# BatteryManagementSystemA.net
KiCad netlist of a schematic drawn in Altium Designer
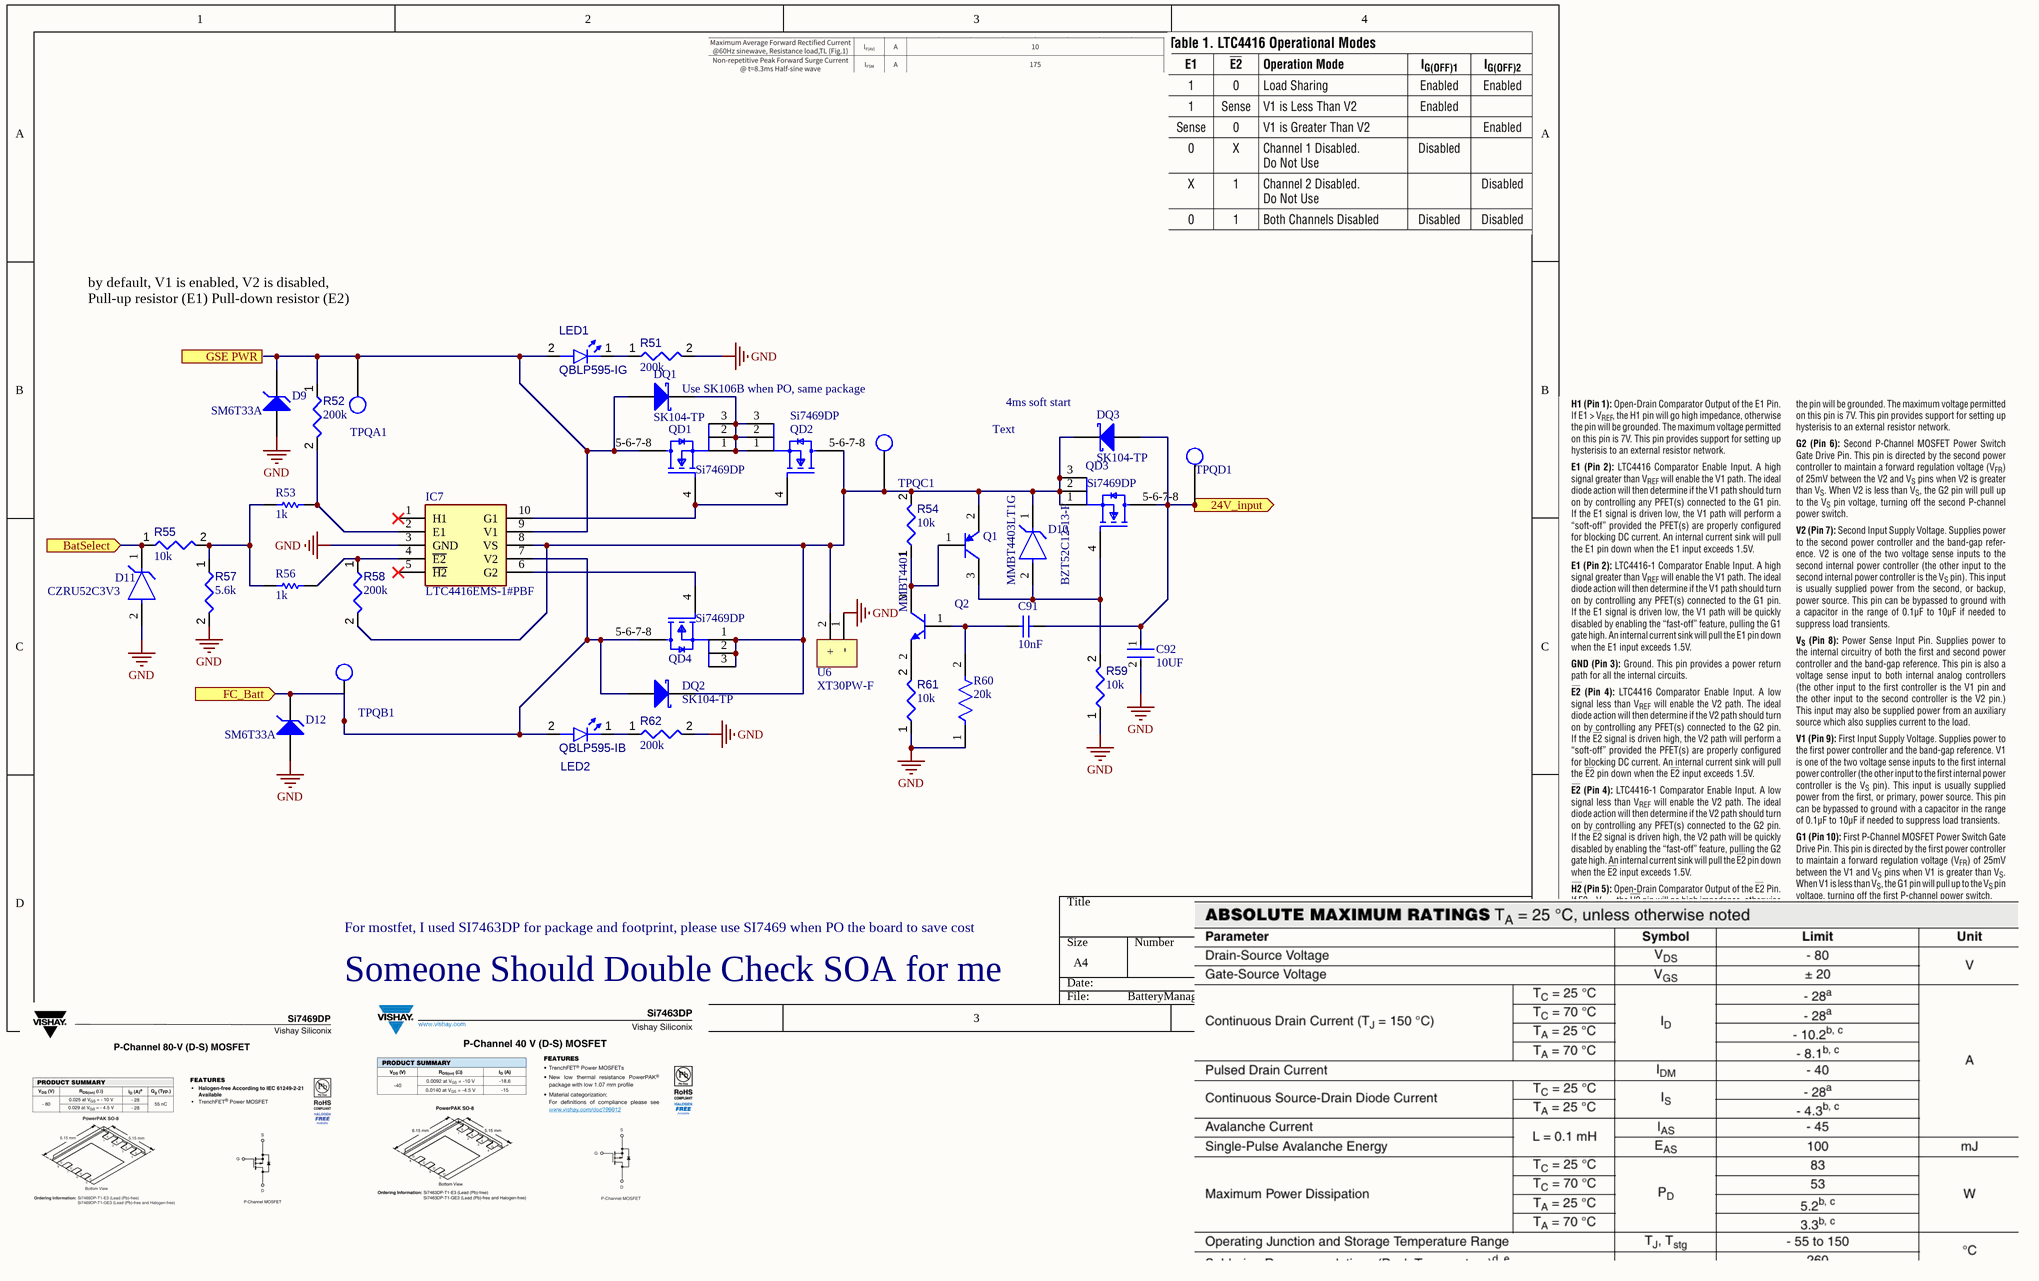
[diagram p0: BatteryManagementSystemA.SchDoc]

(export (version "E")
  (design (tool "Eeschema 10.0.6"))
  (components
    (comp (ref "C91")
      (value "10nF")
      (footprint "CAPC1608X90X35ML10T15")
      (description "Chip Capacitor, 10 nF, +/- 10%, 50 V, -55 to 125 degC, 0603 (1608 Metric), RoHS, Tape and Reel")
      (fields (field (name "VOLTAGE") "50V") (field (name "TOLERANCE") "10%"))
      (libsource (lib "Altium Content Vault") (part "CAP-NP-2"))
    )
    (comp (ref "C92")
      (value "10UF")
      (footprint "FP-GRM31-0_2-MFG")
      (description "CAP CER 10UF 50V X5R 1206")
      (fields
        (field (name "OCTOPART") "https://octopart.com/grm31cr61h106ka12l-murata-18903335")
        (field (name "TOLERANCE") "10%")
      )
      (libsource (lib "Altium Content Vault") (part "11868f565c42a9108669ba33697ecf6"))
    )
    (comp (ref "D9")
      (value "SM6T33A")
      (footprint "STM-SMB_P_V")
      (description "Transil(TM), Uni-Directional, 600 W, -55 to 150 degC, 2-Pin SMB , RoHS, Tape and Reel")
      (fields (field (name "MANUFACTURER") "STMicroelectronics"))
      (libsource (lib "Altium Content Vault") (part "DZEN-KA-2"))
    )
    (comp (ref "D10")
      (value "BZT52C12-13-F")
      (footprint "FP-SOD123-MFG")
      (description "DIODE ZENER 12V 500MW SOD123")
      (fields
        (field (name "OCTOPART") "https://octopart.com/bzt52c12-13-f-diodes+inc.-326533")
        (field (name "MANUFACTURER") "Diodes Inc")
      )
      (libsource (lib "Altium Content Vault") (part "f813f71cba58e380607f5dd3caf9714"))
    )
    (comp (ref "D11")
      (value "CZRU52C3V3")
      (footprint "FP-0603-SOD-523F-MFG")
      (description "DIODE ZENER 3.3V 150MW 0603")
      (fields (field (name "TOLERANCE") "5%"))
      (libsource (lib "Altium Content Vault") (part "f813f71cba58e380607f5dd3caf9714"))
    )
    (comp (ref "D12")
      (value "SM6T33A")
      (footprint "STM-SMB_P_V")
      (description "Transil(TM), Uni-Directional, 600 W, -55 to 150 degC, 2-Pin SMB , RoHS, Tape and Reel")
      (fields (field (name "MANUFACTURER") "STMicroelectronics"))
      (libsource (lib "Altium Content Vault") (part "DZEN-KA-2"))
    )
    (comp (ref "DQ1")
      (value "SK104-TP")
      (footprint "MCC-DO-214AB-2_V")
      (description "Schottky Rectifier, 40 V, 10 A, -55 to 125 degC, 2-Pin SMD, RoHS, Tape and Reel")
      (fields (field (name "MANUFACTURER") "Micro Commercial Components"))
      (libsource (lib "Altium Content Vault") (part "DSKY-AK-2"))
    )
    (comp (ref "DQ2")
      (value "SK104-TP")
      (footprint "MCC-DO-214AB-2_V")
      (description "Schottky Rectifier, 40 V, 10 A, -55 to 125 degC, 2-Pin SMD, RoHS, Tape and Reel")
      (fields (field (name "MANUFACTURER") "Micro Commercial Components"))
      (libsource (lib "Altium Content Vault") (part "DSKY-AK-2"))
    )
    (comp (ref "DQ3")
      (value "SK104-TP")
      (footprint "MCC-DO-214AB-2_V")
      (description "Schottky Rectifier, 40 V, 10 A, -55 to 125 degC, 2-Pin SMD, RoHS, Tape and Reel")
      (fields (field (name "MANUFACTURER") "Micro Commercial Components"))
      (libsource (lib "Altium Content Vault") (part "DSKY-AK-2"))
    )
    (comp (ref "IC7")
      (value "LTC4416EMS-1#PBF")
      (footprint "SamacSys:SOP50P490X110-10N")
      (description "Integrated Circuit")
      (fields (field (name "MOUSER PART NUMBER") "584-LTC4416EMS-1#PBF"))
      (libsource (lib "*") (part "LTC4416EMS-1#PBF"))
    )
    (comp (ref "LED1")
      (value "QBLP595-IG")
      (footprint "QTB-QBLP595_V")
      (description "Chip LED 0402, Green, 0.02 A, 3.1 to 3.7 V, -40 to 80 degC, 2-Pin SMD, RoHS, Tape and Reel")
      (libsource (lib "Yuxuan chen") (part "LED-KA-2"))
    )
    (comp (ref "LED2")
      (value "QBLP595-IB")
      (footprint "QTB-QBLP595_V")
      (description "Chip LED 0402, Blue, 0.02 A, 3.1 to 3.7 V, -40 to 80 degC, 2-Pin SMD, RoHS, Tape and Reel")
      (libsource (lib "Yuxuan chen") (part "LED-KA-2"))
    )
    (comp (ref "Q1")
      (value "MMBT4403LT1G")
      (footprint "ONSC-SOT-23-3-318-08_V")
      (description "Switching Transistor, PNP Silicon, 3-Pin SOT-23, Pb-Free, Tape and Reel")
      (fields (field (name "MANUFACTURER") "On Semiconductor"))
      (libsource (lib "Altium Content Vault") (part "ONSC-PNP-B1E2C3-3"))
    )
    (comp (ref "Q2")
      (value "MMBT4401")
      (footprint "FAIR-SOT23-3_V")
      (description "NPN General-Purpose Amplifier, 0.6 A, 40 V, -55 to 150 degC, 3-Pin SOT-23, RoHS, Tape and Reel")
      (fields (field (name "MANUFACTURER") "FairchildSemiconductor"))
      (libsource (lib "Altium Content Vault") (part "BJT-NPN-BEC-3"))
    )
    (comp (ref "QD1")
      (value "Si7469DP")
      (footprint "FP-S17-0173-SINGLE-MFG")
      (description "Use Si7469DP For PCBA. MOSFET P-CH 40V 11A PPAK SO-8")
      (fields
        (field (name "MANUFACTURER") "Vishay")
        (field (name "OCTOPART") "https://octopart.com/si7463dp-t1-e3-vishay-42065245")
      )
      (libsource (lib "Altium Content Vault") (part "b7bcde56cf7e2f7a604793c3855a7b6"))
    )
    (comp (ref "QD2")
      (value "Si7469DP")
      (footprint "FP-S17-0173-SINGLE-MFG")
      (description "MOSFET P-CH 40V 11A PPAK SO-8")
      (fields
        (field (name "MANUFACTURER") "Vishay")
        (field (name "OCTOPART") "https://octopart.com/si7463dp-t1-e3-vishay-42065245")
      )
      (libsource (lib "Altium Content Vault") (part "b7bcde56cf7e2f7a604793c3855a7b6"))
    )
    (comp (ref "QD3")
      (value "Si7469DP")
      (footprint "FP-S17-0173-SINGLE-MFG")
      (description "Use Si7469DP For PCBA. MOSFET P-CH 40V 11A PPAK SO-8")
      (fields
        (field (name "MANUFACTURER") "Vishay")
        (field (name "OCTOPART") "https://octopart.com/si7463dp-t1-e3-vishay-42065245")
      )
      (libsource (lib "Altium Content Vault") (part "b7bcde56cf7e2f7a604793c3855a7b6"))
    )
    (comp (ref "QD4")
      (value "Si7469DP")
      (footprint "FP-S17-0173-SINGLE-MFG")
      (description "Use Si7469DP For PCBA. MOSFET P-CH 40V 11A PPAK SO-8")
      (fields
        (field (name "MANUFACTURER") "Vishay")
        (field (name "OCTOPART") "https://octopart.com/si7463dp-t1-e3-vishay-42065245")
      )
      (libsource (lib "Altium Content Vault") (part "b7bcde56cf7e2f7a604793c3855a7b6"))
    )
    (comp (ref "R51")
      (value "200k")
      (footprint "RESC1608X55X25ML10T15")
      (description "Chip Resistor, 100 KOhm, +/- 1%, 0.1 W, -55 to 155 degC, 0603 (1608 Metric)")
      (fields (field (name "TOLERANCE") "1%") (field (name "POWER") "100mW"))
      (libsource (lib "Charlie's Workspace") (part "RES-2"))
    )
    (comp (ref "R52")
      (value "200k")
      (footprint "RESC1608X55X25ML10T15")
      (description "Chip Resistor, 100 KOhm, +/- 1%, 0.1 W, -55 to 155 degC, 0603 (1608 Metric)")
      (fields (field (name "TOLERANCE") "1%") (field (name "POWER") "100mW"))
      (libsource (lib "Charlie's Workspace") (part "RES-2"))
    )
    (comp (ref "R53")
      (value "1k")
      (footprint "RESC2013X60X35ML10T20")
      (description "Chip Resistor, 1 KOhm, +/- 1%, 125 mW, -55 to 155 degC, 0805 (2012 Metric), RoHS, Tape and Reel")
      (fields (field (name "TOLERANCE") "1%") (field (name "MANUFACTURER") "Yageo"))
      (libsource (lib "Altium Content Vault") (part "RES-2"))
    )
    (comp (ref "R54")
      (value "10k")
      (footprint "RESC2013X50X35ML15T15")
      (description "Chip Resistor, 10 KOhm, +/- 1%, 125 mW, -55 to 155 degC, 0805 (2012 Metric)")
      (fields (field (name "TOLERANCE") "1%") (field (name "POWER") "125mW"))
      (libsource (lib "Yuxuan chen") (part "RES-2"))
    )
    (comp (ref "R55")
      (value "10k")
      (footprint "RESC1608X55X25ML10T15")
      (description "Chip Resistor, 10 KOhm, +/- 1%, 01 W, -55 to 155 degC, 0603 (1608 Metric)")
      (fields (field (name "POWER") "100mW") (field (name "TOLERANCE") "1%"))
      (libsource (lib "Charlie's Workspace") (part "RES-2"))
    )
    (comp (ref "R56")
      (value "1k")
      (footprint "RESC2013X60X35ML10T20")
      (description "Chip Resistor, 1 KOhm, +/- 1%, 125 mW, -55 to 155 degC, 0805 (2012 Metric), RoHS, Tape and Reel")
      (fields (field (name "TOLERANCE") "1%") (field (name "MANUFACTURER") "Yageo"))
      (libsource (lib "Altium Content Vault") (part "RES-2"))
    )
    (comp (ref "R57")
      (value "5.6k")
      (footprint "RESC1608X55X25ML10T15")
      (description "Chip Resistor, 10 KOhm, +/- 1%, 01 W, -55 to 155 degC, 0603 (1608 Metric)")
      (fields (field (name "POWER") "100mW") (field (name "TOLERANCE") "1%"))
      (libsource (lib "Charlie's Workspace") (part "RES-2"))
    )
    (comp (ref "R58")
      (value "200k")
      (footprint "RESC1608X55X25ML10T15")
      (description "Chip Resistor, 100 KOhm, +/- 1%, 0.1 W, -55 to 155 degC, 0603 (1608 Metric)")
      (fields (field (name "TOLERANCE") "1%") (field (name "POWER") "100mW"))
      (libsource (lib "Charlie's Workspace") (part "RES-2"))
    )
    (comp (ref "R59")
      (value "10k")
      (footprint "RESC2013X50X35ML15T15")
      (description "Chip Resistor, 10 KOhm, +/- 1%, 125 mW, -55 to 155 degC, 0805 (2012 Metric)")
      (fields (field (name "TOLERANCE") "1%") (field (name "POWER") "125mW"))
      (libsource (lib "Yuxuan chen") (part "RES-2"))
    )
    (comp (ref "R60")
      (value "20k")
      (footprint "FP-CRCW0805-e3-MFG")
      (description "RES Thick Film, 20kΩ, 1%, 0.125W, 100ppm/°C, 0805")
      (fields (field (name "TOLERANCE") "1%"))
      (libsource (lib "Altium Content Vault") (part "1029c3af85768c4190bb7ad29bc67b5"))
    )
    (comp (ref "R61")
      (value "10k")
      (footprint "RESC2013X50X35ML15T15")
      (description "Chip Resistor, 10 KOhm, +/- 1%, 125 mW, -55 to 155 degC, 0805 (2012 Metric)")
      (fields (field (name "TOLERANCE") "1%") (field (name "POWER") "125mW"))
      (libsource (lib "Yuxuan chen") (part "RES-2"))
    )
    (comp (ref "R62")
      (value "200k")
      (footprint "RESC1608X55X25ML10T15")
      (description "Chip Resistor, 100 KOhm, +/- 1%, 0.1 W, -55 to 155 degC, 0603 (1608 Metric)")
      (fields (field (name "TOLERANCE") "1%") (field (name "POWER") "100mW"))
      (libsource (lib "Charlie's Workspace") (part "RES-2"))
    )
    (comp (ref "TPQA1")
      (value "BURPG_TestPoint1")
      (footprint "BURPG_TestPoint1")
      (libsource (lib "BURPG_generic") (part "BURPG_TestPoint1"))
    )
    (comp (ref "TPQB1")
      (value "BURPG_TestPoint1")
      (footprint "BURPG_TestPoint1")
      (libsource (lib "BURPG_generic") (part "BURPG_TestPoint1"))
    )
    (comp (ref "TPQC1")
      (value "BURPG_TestPoint1")
      (footprint "BURPG_TestPoint1")
      (libsource (lib "BURPG_generic") (part "BURPG_TestPoint1"))
    )
    (comp (ref "TPQD1")
      (value "BURPG_TestPoint1")
      (footprint "BURPG_TestPoint1")
      (libsource (lib "BURPG_generic") (part "BURPG_TestPoint1"))
    )
    (comp (ref "U6")
      (value "XT30PW-F")
      (footprint "XT30PW-F")
      (libsource (lib "LIN_Library ") (part "XT30PW-F"))
    )
  )
  (nets
    (net (code "1") (name "/24V_input") (class "Default")
      (node (ref "C91") (pin "2") (pinfunction "2_2") (pintype "passive"))
      (node (ref "C92") (pin "1") (pinfunction "1_1") (pintype "passive"))
      (node (ref "DQ3") (pin "1") (pinfunction "A_1") (pintype "passive"))
      (node (ref "QD3") (pin "5-6-7-8") (pinfunction "D_5-6-7-8") (pintype "passive"))
      (node (ref "TPQD1") (pin "1") (pinfunction "1_1") (pintype "passive"))
    )
    (net (code "2") (name "/BatSelect") (class "Default")
      (node (ref "D11") (pin "1") (pinfunction "C_1") (pintype "passive"))
      (node (ref "R55") (pin "1") (pinfunction "1_1") (pintype "passive"))
    )
    (net (code "3") (name "/FC_Batt") (class "Default")
      (node (ref "D12") (pin "1") (pinfunction "K_1") (pintype "passive"))
      (node (ref "DQ2") (pin "1") (pinfunction "A_1") (pintype "passive"))
      (node (ref "IC7") (pin "7") (pinfunction "V2_7") (pintype "passive"))
      (node (ref "LED2") (pin "2") (pinfunction "A_2") (pintype "passive"))
      (node (ref "QD4") (pin "5-6-7-8") (pinfunction "D_5-6-7-8") (pintype "passive"))
      (node (ref "TPQB1") (pin "1") (pinfunction "1_1") (pintype "passive"))
    )
    (net (code "5") (name "GND") (class "Default")
      (node (ref "C92") (pin "2") (pinfunction "2_2") (pintype "passive"))
      (node (ref "D11") (pin "2") (pinfunction "A_2") (pintype "passive"))
      (node (ref "D12") (pin "2") (pinfunction "A_2") (pintype "passive"))
      (node (ref "D9") (pin "2") (pinfunction "A_2") (pintype "passive"))
      (node (ref "IC7") (pin "3") (pinfunction "GND_3") (pintype "passive"))
      (node (ref "R51") (pin "2") (pinfunction "2_2") (pintype "passive"))
      (node (ref "R57") (pin "2") (pinfunction "2_2") (pintype "passive"))
      (node (ref "R59") (pin "1") (pinfunction "1_1") (pintype "passive"))
      (node (ref "R60") (pin "1") (pinfunction "1_1") (pintype "passive"))
      (node (ref "R61") (pin "1") (pinfunction "1_1") (pintype "passive"))
      (node (ref "R62") (pin "2") (pinfunction "2_2") (pintype "passive"))
      (node (ref "U6") (pin "1") (pinfunction "-_1") (pintype "passive"))
    )
    (net (code "6") (name "Net-(D9-K)") (class "Default")
      (node (ref "D9") (pin "1") (pinfunction "K_1") (pintype "passive"))
      (node (ref "DQ1") (pin "1") (pinfunction "A_1") (pintype "passive"))
      (node (ref "IC7") (pin "9") (pinfunction "V1_9") (pintype "passive"))
      (node (ref "LED1") (pin "2") (pinfunction "A_2") (pintype "passive"))
      (node (ref "QD1") (pin "5-6-7-8") (pinfunction "D_5-6-7-8") (pintype "passive"))
      (node (ref "R52") (pin "1") (pinfunction "1_1") (pintype "passive"))
      (node (ref "TPQA1") (pin "1") (pinfunction "1_1") (pintype "passive"))
    )
    (net (code "7") (name "Net-(D10-A)") (class "Default")
      (node (ref "D10") (pin "2") (pinfunction "A_2") (pintype "passive"))
      (node (ref "Q1") (pin "3") (pinfunction "C_3") (pintype "passive"))
      (node (ref "QD3") (pin "4") (pinfunction "G_4") (pintype "passive"))
      (node (ref "R59") (pin "2") (pinfunction "2_2") (pintype "passive"))
    )
    (net (code "8") (name "Net-(D10-C)") (class "Default")
      (node (ref "D10") (pin "1") (pinfunction "C_1") (pintype "passive"))
      (node (ref "DQ2") (pin "2") (pinfunction "K_2") (pintype "passive"))
      (node (ref "DQ3") (pin "2") (pinfunction "K_2") (pintype "passive"))
      (node (ref "IC7") (pin "8") (pinfunction "VS_8") (pintype "passive"))
      (node (ref "Q1") (pin "2") (pinfunction "E_2") (pintype "passive"))
      (node (ref "QD2") (pin "5-6-7-8") (pinfunction "D_5-6-7-8") (pintype "passive"))
      (node (ref "QD3") (pin "1") (pinfunction "S_1") (pintype "passive"))
      (node (ref "QD3") (pin "2") (pinfunction "S_2") (pintype "passive"))
      (node (ref "QD3") (pin "3") (pinfunction "S_3") (pintype "passive"))
      (node (ref "QD4") (pin "1") (pinfunction "S_1") (pintype "passive"))
      (node (ref "QD4") (pin "2") (pinfunction "S_2") (pintype "passive"))
      (node (ref "QD4") (pin "3") (pinfunction "S_3") (pintype "passive"))
      (node (ref "R54") (pin "2") (pinfunction "2_2") (pintype "passive"))
      (node (ref "R58") (pin "2") (pinfunction "2_2") (pintype "passive"))
      (node (ref "TPQC1") (pin "1") (pinfunction "1_1") (pintype "passive"))
      (node (ref "U6") (pin "2") (pinfunction "+_2") (pintype "passive"))
    )
    (net (code "9") (name "Net-(DQ1-K)") (class "Default")
      (node (ref "DQ1") (pin "2") (pinfunction "K_2") (pintype "passive"))
      (node (ref "QD1") (pin "1") (pinfunction "S_1") (pintype "passive"))
      (node (ref "QD1") (pin "2") (pinfunction "S_2") (pintype "passive"))
      (node (ref "QD1") (pin "3") (pinfunction "S_3") (pintype "passive"))
      (node (ref "QD2") (pin "1") (pinfunction "S_1") (pintype "passive"))
      (node (ref "QD2") (pin "2") (pinfunction "S_2") (pintype "passive"))
      (node (ref "QD2") (pin "3") (pinfunction "S_3") (pintype "passive"))
    )
    (net (code "10") (name "Net-(IC7-E1)") (class "Default")
      (node (ref "IC7") (pin "2") (pinfunction "E1_2") (pintype "passive"))
      (node (ref "R52") (pin "2") (pinfunction "2_2") (pintype "passive"))
      (node (ref "R53") (pin "2") (pinfunction "2_2") (pintype "passive"))
    )
    (net (code "11") (name "Net-(IC7-G1)") (class "Default")
      (node (ref "IC7") (pin "10") (pinfunction "G1_10") (pintype "passive"))
      (node (ref "QD1") (pin "4") (pinfunction "G_4") (pintype "passive"))
      (node (ref "QD2") (pin "4") (pinfunction "G_4") (pintype "passive"))
    )
    (net (code "12") (name "Net-(IC7-G2)") (class "Default")
      (node (ref "IC7") (pin "6") (pinfunction "G2_6") (pintype "passive"))
      (node (ref "QD4") (pin "4") (pinfunction "G_4") (pintype "passive"))
    )
    (net (code "13") (name "Net-(IC7-~{E2})") (class "Default")
      (node (ref "IC7") (pin "4") (pinfunction "~{E2}_4") (pintype "passive"))
      (node (ref "R56") (pin "2") (pinfunction "2_2") (pintype "passive"))
      (node (ref "R58") (pin "1") (pinfunction "1_1") (pintype "passive"))
    )
    (net (code "14") (name "Net-(LED1-K)") (class "Default")
      (node (ref "LED1") (pin "1") (pinfunction "K_1") (pintype "passive"))
      (node (ref "R51") (pin "1") (pinfunction "1_1") (pintype "passive"))
    )
    (net (code "15") (name "Net-(LED2-K)") (class "Default")
      (node (ref "LED2") (pin "1") (pinfunction "K_1") (pintype "passive"))
      (node (ref "R62") (pin "1") (pinfunction "1_1") (pintype "passive"))
    )
    (net (code "16") (name "Net-(Q1-B)") (class "Default")
      (node (ref "Q1") (pin "1") (pinfunction "B_1") (pintype "passive"))
      (node (ref "Q2") (pin "3") (pinfunction "C_3") (pintype "passive"))
      (node (ref "R54") (pin "1") (pinfunction "1_1") (pintype "passive"))
    )
    (net (code "17") (name "Net-(Q2-B)") (class "Default")
      (node (ref "C91") (pin "1") (pinfunction "1_1") (pintype "passive"))
      (node (ref "Q2") (pin "1") (pinfunction "B_1") (pintype "passive"))
      (node (ref "R60") (pin "2") (pinfunction "2_2") (pintype "passive"))
    )
    (net (code "18") (name "Net-(Q2-E)") (class "Default")
      (node (ref "Q2") (pin "2") (pinfunction "E_2") (pintype "passive"))
      (node (ref "R61") (pin "2") (pinfunction "2_2") (pintype "passive"))
    )
    (net (code "19") (name "Net-(R53-Pad1)") (class "Default")
      (node (ref "R53") (pin "1") (pinfunction "1_1") (pintype "passive"))
      (node (ref "R55") (pin "2") (pinfunction "2_2") (pintype "passive"))
      (node (ref "R56") (pin "1") (pinfunction "1_1") (pintype "passive"))
      (node (ref "R57") (pin "1") (pinfunction "1_1") (pintype "passive"))
    )
    (net (code "20") (name "unconnected-(IC7-H1-Pad1)") (class "Default")
      (node (ref "IC7") (pin "1") (pinfunction "H1_1") (pintype "passive+no_connect"))
    )
    (net (code "21") (name "unconnected-(IC7-~{H2}-Pad5)") (class "Default")
      (node (ref "IC7") (pin "5") (pinfunction "~{H2}_5") (pintype "passive+no_connect"))
    )
  )
)
